# ZYNQ_JTAG_and_Decoupling.net
KiCad netlist of a schematic drawn in Altium Designer
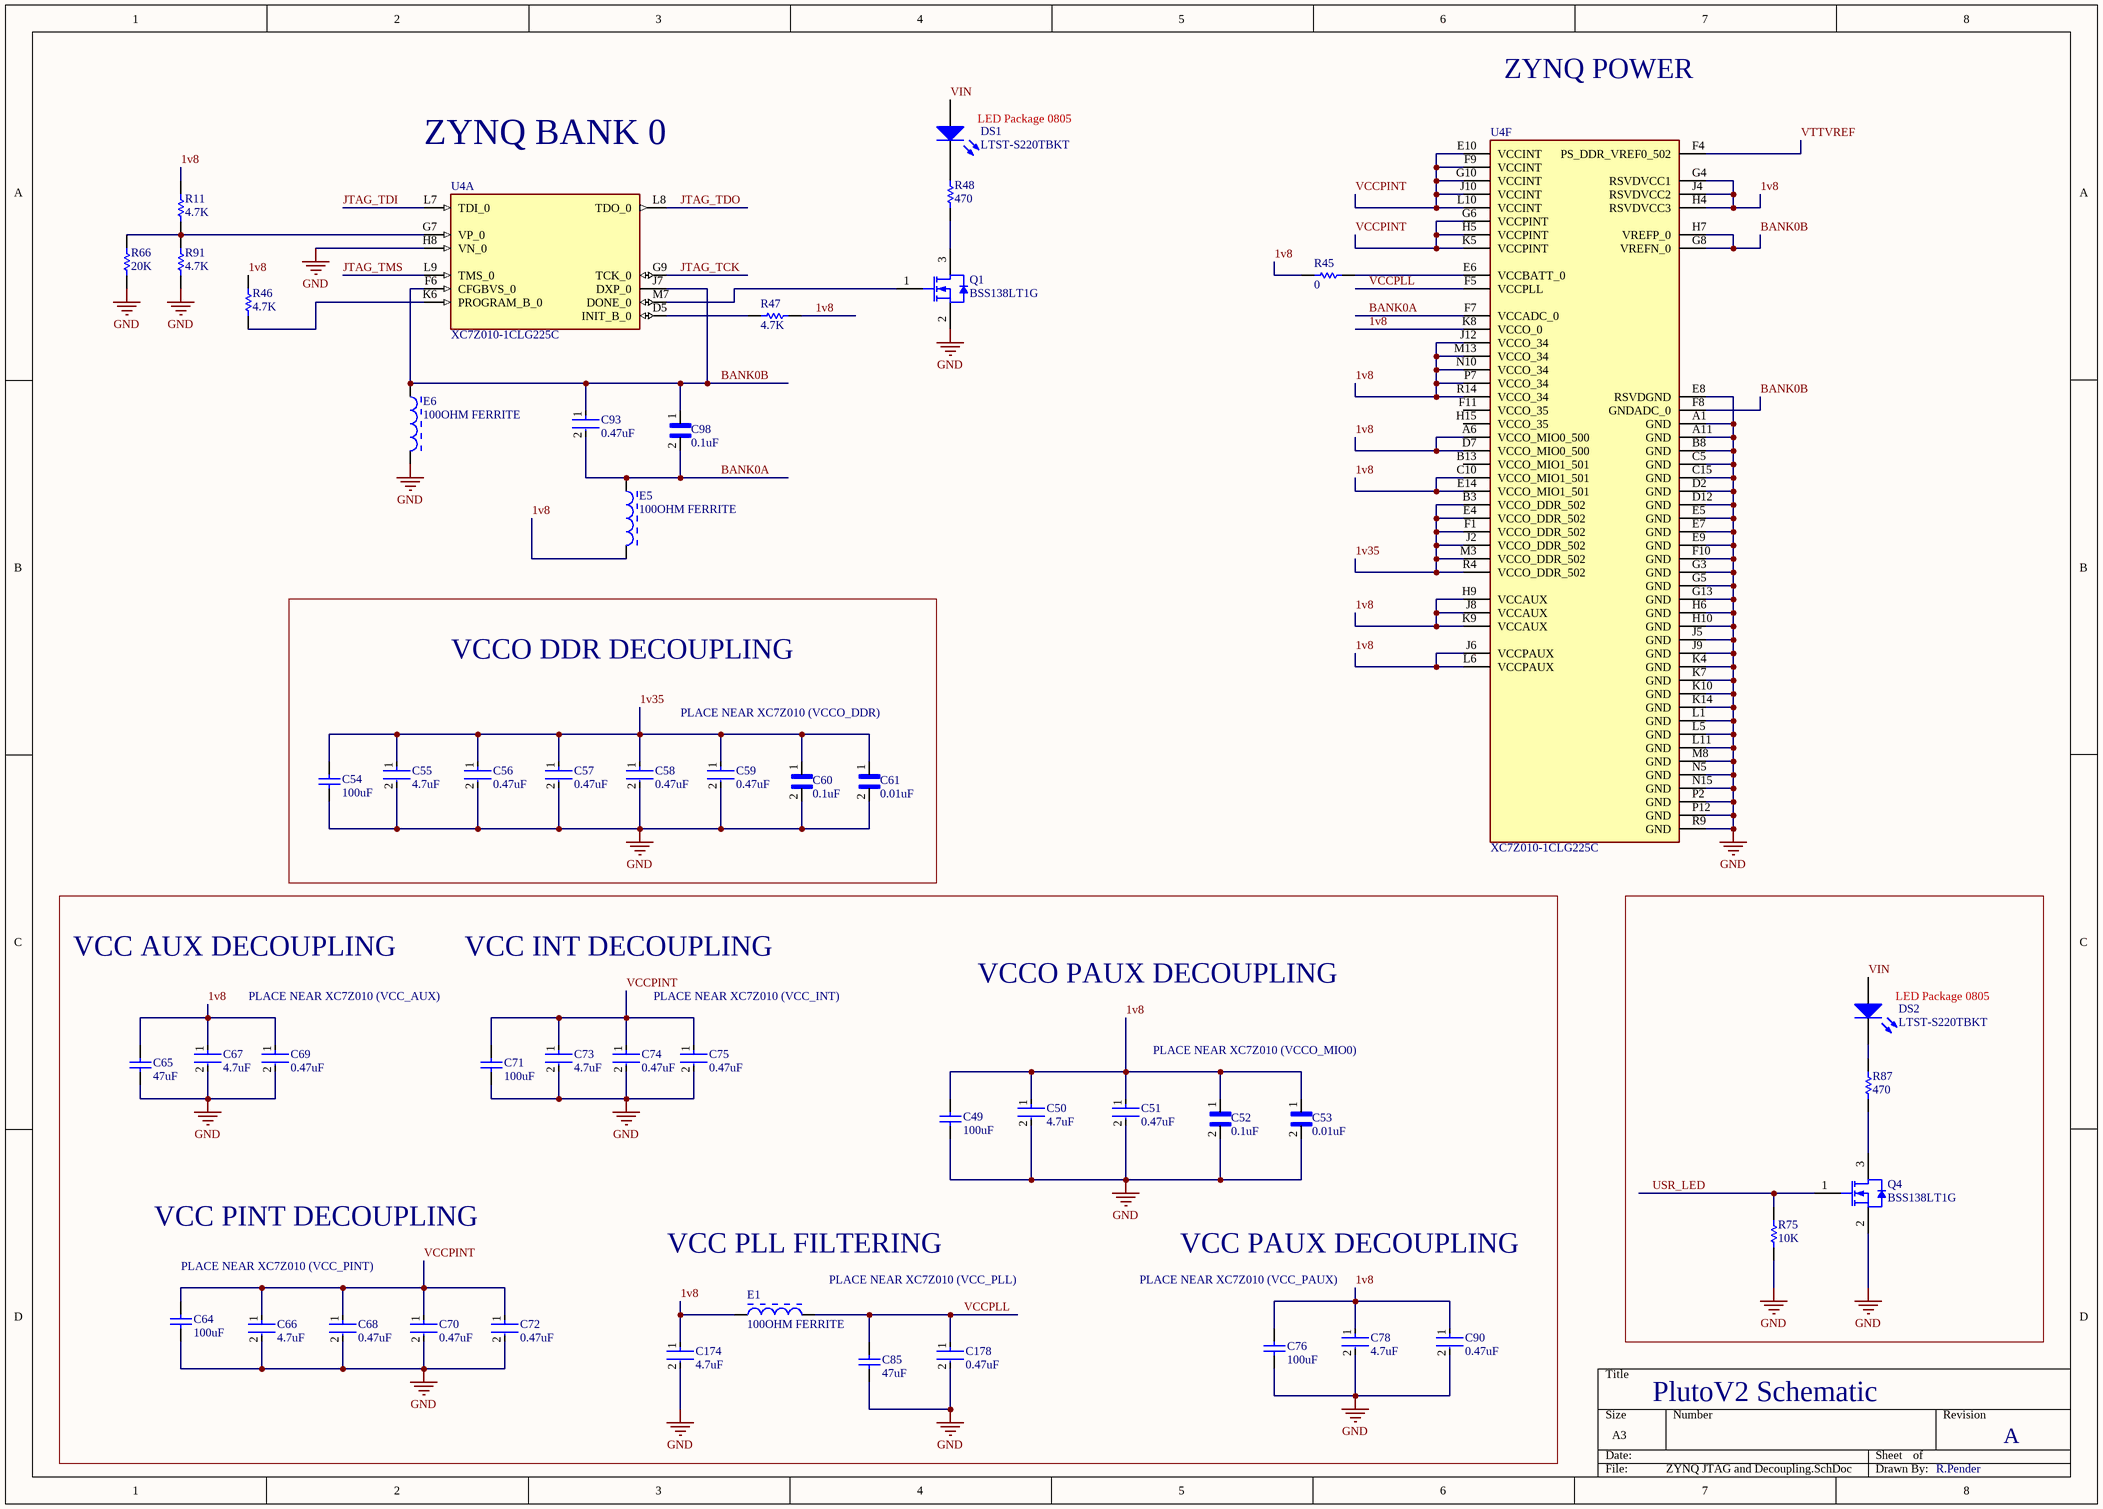
[diagram p0: ZYNQ JTAG and Decoupling.SchDoc]

(export (version "E")
  (design (tool "Eeschema 10.0.6"))
  (components
    (comp (ref "C49")
      (value "100uF")
      (footprint "CAPC3216X190X55ML30T25")
      (description "Chip Capacitor, 100 uF, +/- 20%, 6.3 V, -55 to 85 degC, 1206 (3216 Metric), RoHS, Tape and Reel")
      (fields (field (name "TOLERANCE") "20%") (field (name "PARTNUMBER") "GRM31CR60J107ME39L"))
      (libsource (lib "Altium Content Vault") (part "CAP-NP-2"))
    )
    (comp (ref "C50")
      (value "4.7uF")
      (footprint "FP-C1005-050-0_15-MFG")
      (description "CAP CER 4.7UF 6.3V X5R 0402")
      (fields (field (name "VOLTAGE") "6.3V") (field (name "TOLERANCE") "10%"))
      (libsource (lib "Altium Content Vault") (part "02cd4be3c70576c341d710602a673aa"))
    )
    (comp (ref "C51")
      (value "0.47uF")
      (footprint "FP-C1005-050-0_15-MFG")
      (description "CAP CER 4.7UF 6.3V X5R 0402")
      (fields (field (name "VOLTAGE") "6.3V") (field (name "TOLERANCE") "10%"))
      (libsource (lib "Altium Content Vault") (part "02cd4be3c70576c341d710602a673aa"))
    )
    (comp (ref "C52")
      (value "0.1uF")
      (footprint "CAPC0603X33N")
      (description "CAP 0.1UF 16VDC X5R 20% SMD 0201 PAPER TAPE")
      (fields (field (name "MP") "GRM033R61C104ME84D"))
      (libsource (lib "GRM033R61C104ME84D") (part "GRM033R61C104ME84D"))
    )
    (comp (ref "C53")
      (value "0.01uF")
      (footprint "CAPC0603X33N")
      (description "SMD Capacitor X7R(EIA) with Capacitance: 10000pF Tol. 10%. Rated Voltage: 10Vdc")
      (fields (field (name "MP") "GRM033R71A103KA01D") (field (name "MF") "Murata"))
      (libsource (lib "GRM033R71A103KA01D") (part "GRM033R71A103KA01D"))
    )
    (comp (ref "C54")
      (value "100uF")
      (footprint "CAPC3216X190X55ML30T25")
      (description "Chip Capacitor, 100 uF, +/- 20%, 6.3 V, -55 to 85 degC, 1206 (3216 Metric), RoHS, Tape and Reel")
      (fields (field (name "TOLERANCE") "20%") (field (name "PARTNUMBER") "GRM31CR60J107ME39L"))
      (libsource (lib "Altium Content Vault") (part "CAP-NP-2"))
    )
    (comp (ref "C55")
      (value "4.7uF")
      (footprint "FP-C1005-050-0_15-MFG")
      (description "CAP CER 4.7UF 6.3V X5R 0402")
      (fields (field (name "VOLTAGE") "6.3V") (field (name "TOLERANCE") "10%"))
      (libsource (lib "Altium Content Vault") (part "02cd4be3c70576c341d710602a673aa"))
    )
    (comp (ref "C56")
      (value "0.47uF")
      (footprint "FP-C1005-050-0_15-MFG")
      (description "CAP CER 4.7UF 6.3V X5R 0402")
      (fields (field (name "VOLTAGE") "6.3V") (field (name "TOLERANCE") "10%"))
      (libsource (lib "Altium Content Vault") (part "02cd4be3c70576c341d710602a673aa"))
    )
    (comp (ref "C57")
      (value "0.47uF")
      (footprint "FP-C1005-050-0_15-MFG")
      (description "CAP CER 4.7UF 6.3V X5R 0402")
      (fields (field (name "VOLTAGE") "6.3V") (field (name "TOLERANCE") "10%"))
      (libsource (lib "Altium Content Vault") (part "02cd4be3c70576c341d710602a673aa"))
    )
    (comp (ref "C58")
      (value "0.47uF")
      (footprint "FP-C1005-050-0_15-MFG")
      (description "CAP CER 4.7UF 6.3V X5R 0402")
      (fields (field (name "VOLTAGE") "6.3V") (field (name "TOLERANCE") "10%"))
      (libsource (lib "Altium Content Vault") (part "02cd4be3c70576c341d710602a673aa"))
    )
    (comp (ref "C59")
      (value "0.47uF")
      (footprint "FP-C1005-050-0_15-MFG")
      (description "CAP CER 4.7UF 6.3V X5R 0402")
      (fields (field (name "VOLTAGE") "6.3V") (field (name "TOLERANCE") "10%"))
      (libsource (lib "Altium Content Vault") (part "02cd4be3c70576c341d710602a673aa"))
    )
    (comp (ref "C60")
      (value "0.1uF")
      (footprint "CAPC0603X33N")
      (description "CAP 0.1UF 16VDC X5R 20% SMD 0201 PAPER TAPE")
      (fields (field (name "MP") "GRM033R61C104ME84D"))
      (libsource (lib "GRM033R61C104ME84D") (part "GRM033R61C104ME84D"))
    )
    (comp (ref "C61")
      (value "0.01uF")
      (footprint "CAPC0603X33N")
      (description "SMD Capacitor X7R(EIA) with Capacitance: 10000pF Tol. 10%. Rated Voltage: 10Vdc")
      (fields (field (name "MP") "GRM033R71A103KA01D") (field (name "MF") "Murata"))
      (libsource (lib "GRM033R71A103KA01D") (part "GRM033R71A103KA01D"))
    )
    (comp (ref "C64")
      (value "100uF")
      (footprint "CAPC3216X190X55LL30T25")
      (description "Chip Capacitor, 100 uF, +/- 20%, 6.3 V, -55 to 85 degC, 1206 (3216 Metric), RoHS, Tape and Reel")
      (fields (field (name "TOLERANCE") "20%") (field (name "PARTNUMBER") "GRM31CR60J107ME39L"))
      (libsource (lib "Altium Content Vault") (part "CAP-NP-2"))
    )
    (comp (ref "C65")
      (value "47uF")
      (footprint "TAYO-JMK212BBJ476MG-T_L")
      (fields
        (field (name "MANUFACTURER") "Taiyo Yuden")
        (field (name "TOLERANCE") "±20%")
        (field (name "PCN PART NUMBER") "X5R,X7RDielectrics23/Jan/2008")
      )
      (libsource (lib "Altium Content Vault") (part "CAP-NP-2"))
    )
    (comp (ref "C66")
      (value "4.7uF")
      (footprint "FP-C1005-050-0_15-MFG")
      (description "CAP CER 4.7UF 6.3V X5R 0402")
      (fields (field (name "VOLTAGE") "6.3V") (field (name "TOLERANCE") "10%"))
      (libsource (lib "Altium Content Vault") (part "02cd4be3c70576c341d710602a673aa"))
    )
    (comp (ref "C67")
      (value "4.7uF")
      (footprint "FP-C1005-050-0_15-MFG")
      (description "CAP CER 4.7UF 6.3V X5R 0402")
      (fields (field (name "VOLTAGE") "6.3V") (field (name "TOLERANCE") "10%"))
      (libsource (lib "Altium Content Vault") (part "02cd4be3c70576c341d710602a673aa"))
    )
    (comp (ref "C68")
      (value "0.47uF")
      (footprint "FP-C1005-050-0_15-MFG")
      (description "CAP CER 4.7UF 6.3V X5R 0402")
      (fields (field (name "VOLTAGE") "6.3V") (field (name "TOLERANCE") "10%"))
      (libsource (lib "Altium Content Vault") (part "02cd4be3c70576c341d710602a673aa"))
    )
    (comp (ref "C69")
      (value "0.47uF")
      (footprint "FP-C1005-050-0_15-MFG")
      (description "CAP CER 4.7UF 6.3V X5R 0402")
      (fields (field (name "VOLTAGE") "6.3V") (field (name "TOLERANCE") "10%"))
      (libsource (lib "Altium Content Vault") (part "02cd4be3c70576c341d710602a673aa"))
    )
    (comp (ref "C70")
      (value "0.47uF")
      (footprint "FP-C1005-050-0_15-MFG")
      (description "CAP CER 4.7UF 6.3V X5R 0402")
      (fields (field (name "VOLTAGE") "6.3V") (field (name "TOLERANCE") "10%"))
      (libsource (lib "Altium Content Vault") (part "02cd4be3c70576c341d710602a673aa"))
    )
    (comp (ref "C71")
      (value "100uF")
      (footprint "CAPC3216X190X55LL30T25")
      (description "Chip Capacitor, 100 uF, +/- 20%, 6.3 V, -55 to 85 degC, 1206 (3216 Metric), RoHS, Tape and Reel")
      (fields (field (name "TOLERANCE") "20%") (field (name "PARTNUMBER") "GRM31CR60J107ME39L"))
      (libsource (lib "Altium Content Vault") (part "CAP-NP-2"))
    )
    (comp (ref "C72")
      (value "0.47uF")
      (footprint "FP-C1005-050-0_15-MFG")
      (description "CAP CER 4.7UF 6.3V X5R 0402")
      (fields (field (name "VOLTAGE") "6.3V") (field (name "TOLERANCE") "10%"))
      (libsource (lib "Altium Content Vault") (part "02cd4be3c70576c341d710602a673aa"))
    )
    (comp (ref "C73")
      (value "4.7uF")
      (footprint "FP-C1005-050-0_15-MFG")
      (description "CAP CER 4.7UF 6.3V X5R 0402")
      (fields (field (name "VOLTAGE") "6.3V") (field (name "TOLERANCE") "10%"))
      (libsource (lib "Altium Content Vault") (part "02cd4be3c70576c341d710602a673aa"))
    )
    (comp (ref "C74")
      (value "0.47uF")
      (footprint "FP-C1005-050-0_15-MFG")
      (description "CAP CER 4.7UF 6.3V X5R 0402")
      (fields (field (name "VOLTAGE") "6.3V") (field (name "TOLERANCE") "10%"))
      (libsource (lib "Altium Content Vault") (part "02cd4be3c70576c341d710602a673aa"))
    )
    (comp (ref "C75")
      (value "0.47uF")
      (footprint "FP-C1005-050-0_15-MFG")
      (description "CAP CER 4.7UF 6.3V X5R 0402")
      (fields (field (name "VOLTAGE") "6.3V") (field (name "TOLERANCE") "10%"))
      (libsource (lib "Altium Content Vault") (part "02cd4be3c70576c341d710602a673aa"))
    )
    (comp (ref "C76")
      (value "100uF")
      (footprint "CAPC3216X190X55LL30T25")
      (description "Chip Capacitor, 100 uF, +/- 20%, 6.3 V, -55 to 85 degC, 1206 (3216 Metric), RoHS, Tape and Reel")
      (fields (field (name "TOLERANCE") "20%") (field (name "PARTNUMBER") "GRM31CR60J107ME39L"))
      (libsource (lib "Altium Content Vault") (part "CAP-NP-2"))
    )
    (comp (ref "C78")
      (value "4.7uF")
      (footprint "FP-C1005-050-0_15-MFG")
      (description "CAP CER 4.7UF 6.3V X5R 0402")
      (fields (field (name "VOLTAGE") "6.3V") (field (name "TOLERANCE") "10%"))
      (libsource (lib "Altium Content Vault") (part "02cd4be3c70576c341d710602a673aa"))
    )
    (comp (ref "C85")
      (value "47uF")
      (footprint "TAYO-JMK212BBJ476MG-T_L")
      (fields
        (field (name "MANUFACTURER") "Taiyo Yuden")
        (field (name "TOLERANCE") "±20%")
        (field (name "PCN PART NUMBER") "X5R,X7RDielectrics23/Jan/2008")
      )
      (libsource (lib "Altium Content Vault") (part "CAP-NP-2"))
    )
    (comp (ref "C90")
      (value "0.47uF")
      (footprint "FP-C1005-050-0_15-MFG")
      (description "CAP CER 4.7UF 6.3V X5R 0402")
      (fields (field (name "VOLTAGE") "6.3V") (field (name "TOLERANCE") "10%"))
      (libsource (lib "Altium Content Vault") (part "02cd4be3c70576c341d710602a673aa"))
    )
    (comp (ref "C93")
      (value "0.47uF")
      (footprint "FP-C1005-050-0_15-MFG")
      (description "CAP CER 4.7UF 6.3V X5R 0402")
      (fields (field (name "VOLTAGE") "6.3V") (field (name "TOLERANCE") "10%"))
      (libsource (lib "Altium Content Vault") (part "02cd4be3c70576c341d710602a673aa"))
    )
    (comp (ref "C98")
      (value "0.1uF")
      (footprint "CAPC0603X33N")
      (description "CAP 0.1UF 16VDC X5R 20% SMD 0201 PAPER TAPE")
      (fields (field (name "MP") "GRM033R61C104ME84D"))
      (libsource (lib "GRM033R61C104ME84D") (part "GRM033R61C104ME84D"))
    )
    (comp (ref "C174")
      (value "4.7uF")
      (footprint "FP-C1005-050-0_15-MFG")
      (description "CAP CER 4.7UF 6.3V X5R 0402")
      (fields (field (name "VOLTAGE") "6.3V") (field (name "TOLERANCE") "10%"))
      (libsource (lib "Altium Content Vault") (part "02cd4be3c70576c341d710602a673aa"))
    )
    (comp (ref "C178")
      (value "0.47uF")
      (footprint "FP-C1005-050-0_15-MFG")
      (description "CAP CER 4.7UF 6.3V X5R 0402")
      (fields (field (name "VOLTAGE") "6.3V") (field (name "TOLERANCE") "10%"))
      (libsource (lib "Altium Content Vault") (part "02cd4be3c70576c341d710602a673aa"))
    )
    (comp (ref "DS1")
      (value "LTST-S220TBKT")
      (footprint "CAPC2012X135N")
      (description "Typical BLUE SiC LED")
      (fields (field (name "PUBLISHER") "Altium Limited"))
      (libsource (lib "Miscellaneous Devices") (part "LED3"))
    )
    (comp (ref "DS2")
      (value "LTST-S220TBKT")
      (footprint "CAPC2012X135N")
      (description "Typical BLUE SiC LED")
      (fields (field (name "PUBLISHER") "Altium Limited"))
      (libsource (lib "Miscellaneous Devices") (part "LED3"))
    )
    (comp (ref "E1")
      (value "100OHM FERRITE")
      (footprint "TDK-MPZ2012S101A-2_V")
      (fields (field (name "TOLERANCE") "25%") (field (name "MANUFACTURER") "TDK"))
      (libsource (lib "Altium Content Vault") (part "BEAD-2"))
    )
    (comp (ref "E5")
      (value "100OHM FERRITE")
      (footprint "TDK-MPZ2012S101A-2_V")
      (fields (field (name "TOLERANCE") "25%") (field (name "MANUFACTURER") "TDK"))
      (libsource (lib "Altium Content Vault") (part "BEAD-2"))
    )
    (comp (ref "E6")
      (value "100OHM FERRITE")
      (footprint "TDK-MPZ2012S101A-2_V")
      (fields (field (name "TOLERANCE") "25%") (field (name "MANUFACTURER") "TDK"))
      (libsource (lib "Altium Content Vault") (part "BEAD-2"))
    )
    (comp (ref "Q1")
      (value "BSS138LT1G")
      (footprint "ONSC-SOT-23-3-318-08_V")
      (description "Power MOSFET, 200 mA, 50 V, N-Channel, 3-Pin SOT-23, Pb-Free, Tape and Reel")
      (fields (field (name "MANUFACTURER") "On Semiconductor"))
      (libsource (lib "Altium Content Vault") (part "ONSC-NMOS-G1S2D3-3"))
    )
    (comp (ref "Q4")
      (value "BSS138LT1G")
      (footprint "ONSC-SOT-23-3-318-08_V")
      (description "Power MOSFET, 200 mA, 50 V, N-Channel, 3-Pin SOT-23, Pb-Free, Tape and Reel")
      (fields (field (name "MANUFACTURER") "On Semiconductor"))
      (libsource (lib "Altium Content Vault") (part "ONSC-NMOS-G1S2D3-3"))
    )
    (comp (ref "R11")
      (value "4.7K")
      (footprint "2-0402")
      (fields (field (name "PUBLISHER") "Altium Limited"))
      (libsource (lib "Panasonic Resistor") (part "ERJ2RK"))
    )
    (comp (ref "R45")
      (value "0")
      (footprint "RESC1005X40X25ML10T10")
      (fields (field (name "PART NUMBER") "MC00625W040210R") (field (name "MANUFACTURER") "Multicomp"))
      (libsource (lib "Altium Content Vault") (part "RES"))
    )
    (comp (ref "R46")
      (value "4.7K")
      (footprint "2-0402")
      (fields (field (name "PUBLISHER") "Altium Limited"))
      (libsource (lib "Panasonic Resistor") (part "ERJ2RK"))
    )
    (comp (ref "R47")
      (value "4.7K")
      (footprint "2-0402")
      (fields (field (name "PUBLISHER") "Altium Limited"))
      (libsource (lib "Panasonic Resistor") (part "ERJ2RK"))
    )
    (comp (ref "R48")
      (value "470")
      (footprint "2-0402")
      (description "Thick Film Chip Resistor, 1 Ohm to 2.2M Ohm Range, 5% Tolerance, 0402 Size, 0.063 W")
      (fields (field (name "PUBLISHER") "Altium Limited"))
      (libsource (lib "Panasonic Resistor") (part "ERJ2GE"))
    )
    (comp (ref "R66")
      (value "20K")
      (footprint "2-0402")
      (fields (field (name "PUBLISHER") "Altium Limited"))
      (libsource (lib "Panasonic Resistor") (part "ERJ2RK"))
    )
    (comp (ref "R75")
      (value "10K")
      (footprint "2-0402")
      (fields (field (name "PUBLISHER") "Altium Limited"))
      (libsource (lib "Panasonic Resistor") (part "ERJ2RK"))
    )
    (comp (ref "R87")
      (value "470")
      (footprint "2-0402")
      (description "Thick Film Chip Resistor, 1 Ohm to 2.2M Ohm Range, 5% Tolerance, 0402 Size, 0.063 W")
      (fields (field (name "PUBLISHER") "Altium Limited"))
      (libsource (lib "Panasonic Resistor") (part "ERJ2GE"))
    )
    (comp (ref "R91")
      (value "4.7K")
      (footprint "2-0402")
      (fields (field (name "PUBLISHER") "Altium Limited"))
      (libsource (lib "Panasonic Resistor") (part "ERJ2RK"))
    )
    (comp (ref "U4")
      (value "XC7Z010-1CLG225C")
      (footprint "BGA225C80P15X15_1300X1300X150")
      (fields (field (name "MF") "Xilinx Inc.") (field (name "DIGI-KEY_PART_NUMBER") "122-1855-ND"))
      (libsource (lib "XC7Z010-1CLG225C") (part "XC7Z010-1CLG225C"))
    )
  )
  (nets
    (net (code "1") (name "/1v8") (class "Default")
      (node (ref "C174") (pin "1") (pinfunction "1_1") (pintype "passive"))
      (node (ref "C49") (pin "1") (pinfunction "1_1") (pintype "passive"))
      (node (ref "C50") (pin "1") (pinfunction "1_1") (pintype "passive"))
      (node (ref "C51") (pin "1") (pinfunction "1_1") (pintype "passive"))
      (node (ref "C52") (pin "1") (pinfunction "1_1") (pintype "passive"))
      (node (ref "C53") (pin "1") (pinfunction "1_1") (pintype "passive"))
      (node (ref "C65") (pin "1") (pinfunction "1_1") (pintype "passive"))
      (node (ref "C67") (pin "1") (pinfunction "1_1") (pintype "passive"))
      (node (ref "C69") (pin "1") (pinfunction "1_1") (pintype "passive"))
      (node (ref "C76") (pin "1") (pinfunction "1_1") (pintype "passive"))
      (node (ref "C78") (pin "1") (pinfunction "1_1") (pintype "passive"))
      (node (ref "C90") (pin "1") (pinfunction "1_1") (pintype "passive"))
      (node (ref "E1") (pin "1") (pinfunction "1_1") (pintype "passive"))
      (node (ref "E5") (pin "2") (pinfunction "2_2") (pintype "passive"))
      (node (ref "R11") (pin "1") (pinfunction "1_1") (pintype "passive"))
      (node (ref "R45") (pin "1") (pinfunction "1_1") (pintype "passive"))
      (node (ref "R46") (pin "1") (pinfunction "1_1") (pintype "passive"))
      (node (ref "R47") (pin "1") (pinfunction "1_1") (pintype "passive"))
      (node (ref "U4") (pin "A6") (pinfunction "VCCO_MIO0_500_A6") (pintype "power_in"))
      (node (ref "U4") (pin "C10") (pinfunction "VCCO_MIO1_501_C10") (pintype "power_in"))
      (node (ref "U4") (pin "D7") (pinfunction "VCCO_MIO0_500_D7") (pintype "power_in"))
      (node (ref "U4") (pin "E14") (pinfunction "VCCO_MIO1_501_E14") (pintype "power_in"))
      (node (ref "U4") (pin "G4") (pinfunction "RSVDVCC1_G4") (pintype "power_in"))
      (node (ref "U4") (pin "H4") (pinfunction "RSVDVCC3_H4") (pintype "power_in"))
      (node (ref "U4") (pin "H9") (pinfunction "VCCAUX_H9") (pintype "power_in"))
      (node (ref "U4") (pin "J12") (pinfunction "VCCO_34_J12") (pintype "power_in"))
      (node (ref "U4") (pin "J4") (pinfunction "RSVDVCC2_J4") (pintype "power_in"))
      (node (ref "U4") (pin "J6") (pinfunction "VCCPAUX_J6") (pintype "power_in"))
      (node (ref "U4") (pin "J8") (pinfunction "VCCAUX_J8") (pintype "power_in"))
      (node (ref "U4") (pin "K8") (pinfunction "VCCO_0_K8") (pintype "power_in"))
      (node (ref "U4") (pin "K9") (pinfunction "VCCAUX_K9") (pintype "power_in"))
      (node (ref "U4") (pin "L6") (pinfunction "VCCPAUX_L6") (pintype "power_in"))
      (node (ref "U4") (pin "M13") (pinfunction "VCCO_34_M13") (pintype "power_in"))
      (node (ref "U4") (pin "N10") (pinfunction "VCCO_34_N10") (pintype "power_in"))
      (node (ref "U4") (pin "P7") (pinfunction "VCCO_34_P7") (pintype "power_in"))
      (node (ref "U4") (pin "R14") (pinfunction "VCCO_34_R14") (pintype "power_in"))
    )
    (net (code "2") (name "/1v35") (class "Default")
      (node (ref "C54") (pin "2") (pinfunction "2_2") (pintype "passive"))
      (node (ref "C55") (pin "1") (pinfunction "1_1") (pintype "passive"))
      (node (ref "C56") (pin "1") (pinfunction "1_1") (pintype "passive"))
      (node (ref "C57") (pin "1") (pinfunction "1_1") (pintype "passive"))
      (node (ref "C58") (pin "1") (pinfunction "1_1") (pintype "passive"))
      (node (ref "C59") (pin "1") (pinfunction "1_1") (pintype "passive"))
      (node (ref "C60") (pin "1") (pinfunction "1_1") (pintype "passive"))
      (node (ref "C61") (pin "1") (pinfunction "1_1") (pintype "passive"))
      (node (ref "U4") (pin "B3") (pinfunction "VCCO_DDR_502_B3") (pintype "power_in"))
      (node (ref "U4") (pin "E4") (pinfunction "VCCO_DDR_502_E4") (pintype "power_in"))
      (node (ref "U4") (pin "F1") (pinfunction "VCCO_DDR_502_F1") (pintype "power_in"))
      (node (ref "U4") (pin "J2") (pinfunction "VCCO_DDR_502_J2") (pintype "power_in"))
      (node (ref "U4") (pin "M3") (pinfunction "VCCO_DDR_502_M3") (pintype "power_in"))
      (node (ref "U4") (pin "R4") (pinfunction "VCCO_DDR_502_R4") (pintype "power_in"))
    )
    (net (code "3") (name "/BANK0A") (class "Default")
      (node (ref "C93") (pin "2") (pinfunction "2_2") (pintype "passive"))
      (node (ref "C98") (pin "2") (pinfunction "2_2") (pintype "passive"))
      (node (ref "E5") (pin "1") (pinfunction "1_1") (pintype "passive"))
      (node (ref "U4") (pin "F7") (pinfunction "VCCADC_0_F7") (pintype "power_in"))
    )
    (net (code "4") (name "/BANK0B") (class "Default")
      (node (ref "C93") (pin "1") (pinfunction "1_1") (pintype "passive"))
      (node (ref "C98") (pin "1") (pinfunction "1_1") (pintype "passive"))
      (node (ref "E6") (pin "1") (pinfunction "1_1") (pintype "passive"))
      (node (ref "U4") (pin "F6") (pinfunction "CFGBVS_0_F6") (pintype "input"))
      (node (ref "U4") (pin "F8") (pinfunction "GNDADC_0_F8") (pintype "power_in"))
      (node (ref "U4") (pin "G8") (pinfunction "VREFN_0_G8") (pintype "power_in"))
      (node (ref "U4") (pin "H7") (pinfunction "VREFP_0_H7") (pintype "power_in"))
      (node (ref "U4") (pin "J7") (pinfunction "DXP_0_J7") (pintype "passive"))
    )
    (net (code "5") (name "/JTAG_TCK") (class "Default")
      (node (ref "U4") (pin "G9") (pinfunction "TCK_0_G9") (pintype "bidirectional"))
    )
    (net (code "6") (name "/JTAG_TDI") (class "Default")
      (node (ref "U4") (pin "L7") (pinfunction "TDI_0_L7") (pintype "input"))
    )
    (net (code "7") (name "/JTAG_TDO") (class "Default")
      (node (ref "U4") (pin "L8") (pinfunction "TDO_0_L8") (pintype "output"))
    )
    (net (code "8") (name "/JTAG_TMS") (class "Default")
      (node (ref "U4") (pin "L9") (pinfunction "TMS_0_L9") (pintype "input"))
    )
    (net (code "9") (name "/USR_LED") (class "Default")
      (node (ref "Q4") (pin "1") (pinfunction "G_1") (pintype "passive"))
      (node (ref "R75") (pin "1") (pinfunction "1_1") (pintype "passive"))
    )
    (net (code "10") (name "/VCCPINT") (class "Default")
      (node (ref "C64") (pin "2") (pinfunction "2_2") (pintype "passive"))
      (node (ref "C66") (pin "1") (pinfunction "1_1") (pintype "passive"))
      (node (ref "C68") (pin "1") (pinfunction "1_1") (pintype "passive"))
      (node (ref "C70") (pin "1") (pinfunction "1_1") (pintype "passive"))
      (node (ref "C71") (pin "2") (pinfunction "2_2") (pintype "passive"))
      (node (ref "C72") (pin "1") (pinfunction "1_1") (pintype "passive"))
      (node (ref "C73") (pin "1") (pinfunction "1_1") (pintype "passive"))
      (node (ref "C74") (pin "1") (pinfunction "1_1") (pintype "passive"))
      (node (ref "C75") (pin "1") (pinfunction "1_1") (pintype "passive"))
      (node (ref "U4") (pin "E10") (pinfunction "VCCINT_E10") (pintype "power_in"))
      (node (ref "U4") (pin "F9") (pinfunction "VCCINT_F9") (pintype "power_in"))
      (node (ref "U4") (pin "G10") (pinfunction "VCCINT_G10") (pintype "power_in"))
      (node (ref "U4") (pin "G6") (pinfunction "VCCPINT_G6") (pintype "power_in"))
      (node (ref "U4") (pin "H5") (pinfunction "VCCPINT_H5") (pintype "power_in"))
      (node (ref "U4") (pin "J10") (pinfunction "VCCINT_J10") (pintype "power_in"))
      (node (ref "U4") (pin "K5") (pinfunction "VCCPINT_K5") (pintype "power_in"))
      (node (ref "U4") (pin "L10") (pinfunction "VCCINT_L10") (pintype "power_in"))
    )
    (net (code "11") (name "/VCCPLL") (class "Default")
      (node (ref "C178") (pin "1") (pinfunction "1_1") (pintype "passive"))
      (node (ref "C85") (pin "2") (pinfunction "2_2") (pintype "passive"))
      (node (ref "E1") (pin "2") (pinfunction "2_2") (pintype "passive"))
      (node (ref "U4") (pin "F5") (pinfunction "VCCPLL_F5") (pintype "power_in"))
    )
    (net (code "12") (name "/VIN") (class "Default")
      (node (ref "DS1") (pin "1") (pinfunction "A_1") (pintype "passive"))
      (node (ref "DS2") (pin "1") (pinfunction "A_1") (pintype "passive"))
    )
    (net (code "13") (name "/VTTVREF") (class "Default")
      (node (ref "U4") (pin "F4") (pinfunction "PS_DDR_VREF0_502_F4") (pintype "power_in"))
    )
    (net (code "14") (name "GND") (class "Default")
      (node (ref "C174") (pin "2") (pinfunction "2_2") (pintype "passive"))
      (node (ref "C178") (pin "2") (pinfunction "2_2") (pintype "passive"))
      (node (ref "C49") (pin "2") (pinfunction "2_2") (pintype "passive"))
      (node (ref "C50") (pin "2") (pinfunction "2_2") (pintype "passive"))
      (node (ref "C51") (pin "2") (pinfunction "2_2") (pintype "passive"))
      (node (ref "C52") (pin "2") (pinfunction "2_2") (pintype "passive"))
      (node (ref "C53") (pin "2") (pinfunction "2_2") (pintype "passive"))
      (node (ref "C54") (pin "1") (pinfunction "1_1") (pintype "passive"))
      (node (ref "C55") (pin "2") (pinfunction "2_2") (pintype "passive"))
      (node (ref "C56") (pin "2") (pinfunction "2_2") (pintype "passive"))
      (node (ref "C57") (pin "2") (pinfunction "2_2") (pintype "passive"))
      (node (ref "C58") (pin "2") (pinfunction "2_2") (pintype "passive"))
      (node (ref "C59") (pin "2") (pinfunction "2_2") (pintype "passive"))
      (node (ref "C60") (pin "2") (pinfunction "2_2") (pintype "passive"))
      (node (ref "C61") (pin "2") (pinfunction "2_2") (pintype "passive"))
      (node (ref "C64") (pin "1") (pinfunction "1_1") (pintype "passive"))
      (node (ref "C65") (pin "2") (pinfunction "2_2") (pintype "passive"))
      (node (ref "C66") (pin "2") (pinfunction "2_2") (pintype "passive"))
      (node (ref "C67") (pin "2") (pinfunction "2_2") (pintype "passive"))
      (node (ref "C68") (pin "2") (pinfunction "2_2") (pintype "passive"))
      (node (ref "C69") (pin "2") (pinfunction "2_2") (pintype "passive"))
      (node (ref "C70") (pin "2") (pinfunction "2_2") (pintype "passive"))
      (node (ref "C71") (pin "1") (pinfunction "1_1") (pintype "passive"))
      (node (ref "C72") (pin "2") (pinfunction "2_2") (pintype "passive"))
      (node (ref "C73") (pin "2") (pinfunction "2_2") (pintype "passive"))
      (node (ref "C74") (pin "2") (pinfunction "2_2") (pintype "passive"))
      (node (ref "C75") (pin "2") (pinfunction "2_2") (pintype "passive"))
      (node (ref "C76") (pin "2") (pinfunction "2_2") (pintype "passive"))
      (node (ref "C78") (pin "2") (pinfunction "2_2") (pintype "passive"))
      (node (ref "C85") (pin "1") (pinfunction "1_1") (pintype "passive"))
      (node (ref "C90") (pin "2") (pinfunction "2_2") (pintype "passive"))
      (node (ref "E6") (pin "2") (pinfunction "2_2") (pintype "passive"))
      (node (ref "Q1") (pin "2") (pinfunction "S_2") (pintype "passive"))
      (node (ref "Q4") (pin "2") (pinfunction "S_2") (pintype "passive"))
      (node (ref "R66") (pin "2") (pinfunction "2_2") (pintype "passive"))
      (node (ref "R75") (pin "2") (pinfunction "2_2") (pintype "passive"))
      (node (ref "R91") (pin "2") (pinfunction "2_2") (pintype "passive"))
      (node (ref "U4") (pin "A1") (pinfunction "GND_A1") (pintype "power_in"))
      (node (ref "U4") (pin "A11") (pinfunction "GND_A11") (pintype "power_in"))
      (node (ref "U4") (pin "B8") (pinfunction "GND_B8") (pintype "power_in"))
      (node (ref "U4") (pin "C15") (pinfunction "GND_C15") (pintype "power_in"))
      (node (ref "U4") (pin "C5") (pinfunction "GND_C5") (pintype "power_in"))
      (node (ref "U4") (pin "D12") (pinfunction "GND_D12") (pintype "power_in"))
      (node (ref "U4") (pin "D2") (pinfunction "GND_D2") (pintype "power_in"))
      (node (ref "U4") (pin "E5") (pinfunction "GND_E5") (pintype "power_in"))
      (node (ref "U4") (pin "E7") (pinfunction "GND_E7") (pintype "power_in"))
      (node (ref "U4") (pin "E8") (pinfunction "RSVDGND_E8") (pintype "power_in"))
      (node (ref "U4") (pin "E9") (pinfunction "GND_E9") (pintype "power_in"))
      (node (ref "U4") (pin "F10") (pinfunction "GND_F10") (pintype "power_in"))
      (node (ref "U4") (pin "G13") (pinfunction "GND_G13") (pintype "power_in"))
      (node (ref "U4") (pin "G3") (pinfunction "GND_G3") (pintype "power_in"))
      (node (ref "U4") (pin "G5") (pinfunction "GND_G5") (pintype "power_in"))
      (node (ref "U4") (pin "H10") (pinfunction "GND_H10") (pintype "power_in"))
      (node (ref "U4") (pin "H6") (pinfunction "GND_H6") (pintype "power_in"))
      (node (ref "U4") (pin "H8") (pinfunction "VN_0_H8") (pintype "input"))
      (node (ref "U4") (pin "J5") (pinfunction "GND_J5") (pintype "power_in"))
      (node (ref "U4") (pin "J9") (pinfunction "GND_J9") (pintype "power_in"))
      (node (ref "U4") (pin "K10") (pinfunction "GND_K10") (pintype "power_in"))
      (node (ref "U4") (pin "K14") (pinfunction "GND_K14") (pintype "power_in"))
      (node (ref "U4") (pin "K4") (pinfunction "GND_K4") (pintype "power_in"))
      (node (ref "U4") (pin "K7") (pinfunction "GND_K7") (pintype "power_in"))
      (node (ref "U4") (pin "L1") (pinfunction "GND_L1") (pintype "power_in"))
      (node (ref "U4") (pin "L11") (pinfunction "GND_L11") (pintype "power_in"))
      (node (ref "U4") (pin "L5") (pinfunction "GND_L5") (pintype "power_in"))
      (node (ref "U4") (pin "M8") (pinfunction "GND_M8") (pintype "power_in"))
      (node (ref "U4") (pin "N15") (pinfunction "GND_N15") (pintype "power_in"))
      (node (ref "U4") (pin "N5") (pinfunction "GND_N5") (pintype "power_in"))
      (node (ref "U4") (pin "P12") (pinfunction "GND_P12") (pintype "power_in"))
      (node (ref "U4") (pin "P2") (pinfunction "GND_P2") (pintype "power_in"))
      (node (ref "U4") (pin "R9") (pinfunction "GND_R9") (pintype "power_in"))
    )
    (net (code "15") (name "Net-(DS1-K)") (class "Default")
      (node (ref "DS1") (pin "2") (pinfunction "K_2") (pintype "passive"))
      (node (ref "R48") (pin "1") (pinfunction "1_1") (pintype "passive"))
    )
    (net (code "16") (name "Net-(DS2-K)") (class "Default")
      (node (ref "DS2") (pin "2") (pinfunction "K_2") (pintype "passive"))
      (node (ref "R87") (pin "1") (pinfunction "1_1") (pintype "passive"))
    )
    (net (code "17") (name "Net-(Q1-D)") (class "Default")
      (node (ref "Q1") (pin "3") (pinfunction "D_3") (pintype "passive"))
      (node (ref "R48") (pin "2") (pinfunction "2_2") (pintype "passive"))
    )
    (net (code "18") (name "Net-(Q1-G)") (class "Default")
      (node (ref "Q1") (pin "1") (pinfunction "G_1") (pintype "passive"))
      (node (ref "U4") (pin "M7") (pinfunction "DONE_0_M7") (pintype "bidirectional"))
    )
    (net (code "19") (name "Net-(Q4-D)") (class "Default")
      (node (ref "Q4") (pin "3") (pinfunction "D_3") (pintype "passive"))
      (node (ref "R87") (pin "2") (pinfunction "2_2") (pintype "passive"))
    )
    (net (code "20") (name "Net-(U4A-INIT_B_0)") (class "Default")
      (node (ref "R47") (pin "2") (pinfunction "2_2") (pintype "passive"))
      (node (ref "U4") (pin "D5") (pinfunction "INIT_B_0_D5") (pintype "bidirectional"))
    )
    (net (code "21") (name "Net-(U4A-PROGRAM_B_0)") (class "Default")
      (node (ref "R46") (pin "2") (pinfunction "2_2") (pintype "passive"))
      (node (ref "U4") (pin "K6") (pinfunction "PROGRAM_B_0_K6") (pintype "input"))
    )
    (net (code "22") (name "Net-(U4A-VP_0)") (class "Default")
      (node (ref "R11") (pin "2") (pinfunction "2_2") (pintype "passive"))
      (node (ref "R66") (pin "1") (pinfunction "1_1") (pintype "passive"))
      (node (ref "R91") (pin "1") (pinfunction "1_1") (pintype "passive"))
      (node (ref "U4") (pin "G7") (pinfunction "VP_0_G7") (pintype "input"))
    )
    (net (code "23") (name "Net-(U4F-VCCBATT_0)") (class "Default")
      (node (ref "R45") (pin "2") (pinfunction "2_2") (pintype "passive"))
      (node (ref "U4") (pin "E6") (pinfunction "VCCBATT_0_E6") (pintype "power_in"))
    )
    (net (code "24") (name "unconnected-(U4F-VCCO_35-PadF11)") (class "Default")
      (node (ref "U4") (pin "F11") (pinfunction "VCCO_35_F11") (pintype "power_in"))
    )
    (net (code "25") (name "unconnected-(U4F-VCCO_35-PadH15)") (class "Default")
      (node (ref "U4") (pin "H15") (pinfunction "VCCO_35_H15") (pintype "power_in"))
    )
    (net (code "26") (name "unconnected-(U4F-VCCO_MIO1_501-PadB13)") (class "Default")
      (node (ref "U4") (pin "B13") (pinfunction "VCCO_MIO1_501_B13") (pintype "power_in"))
    )
  )
)
